# connectors-extension.net
KiCad netlist of a schematic drawn in Altium Designer
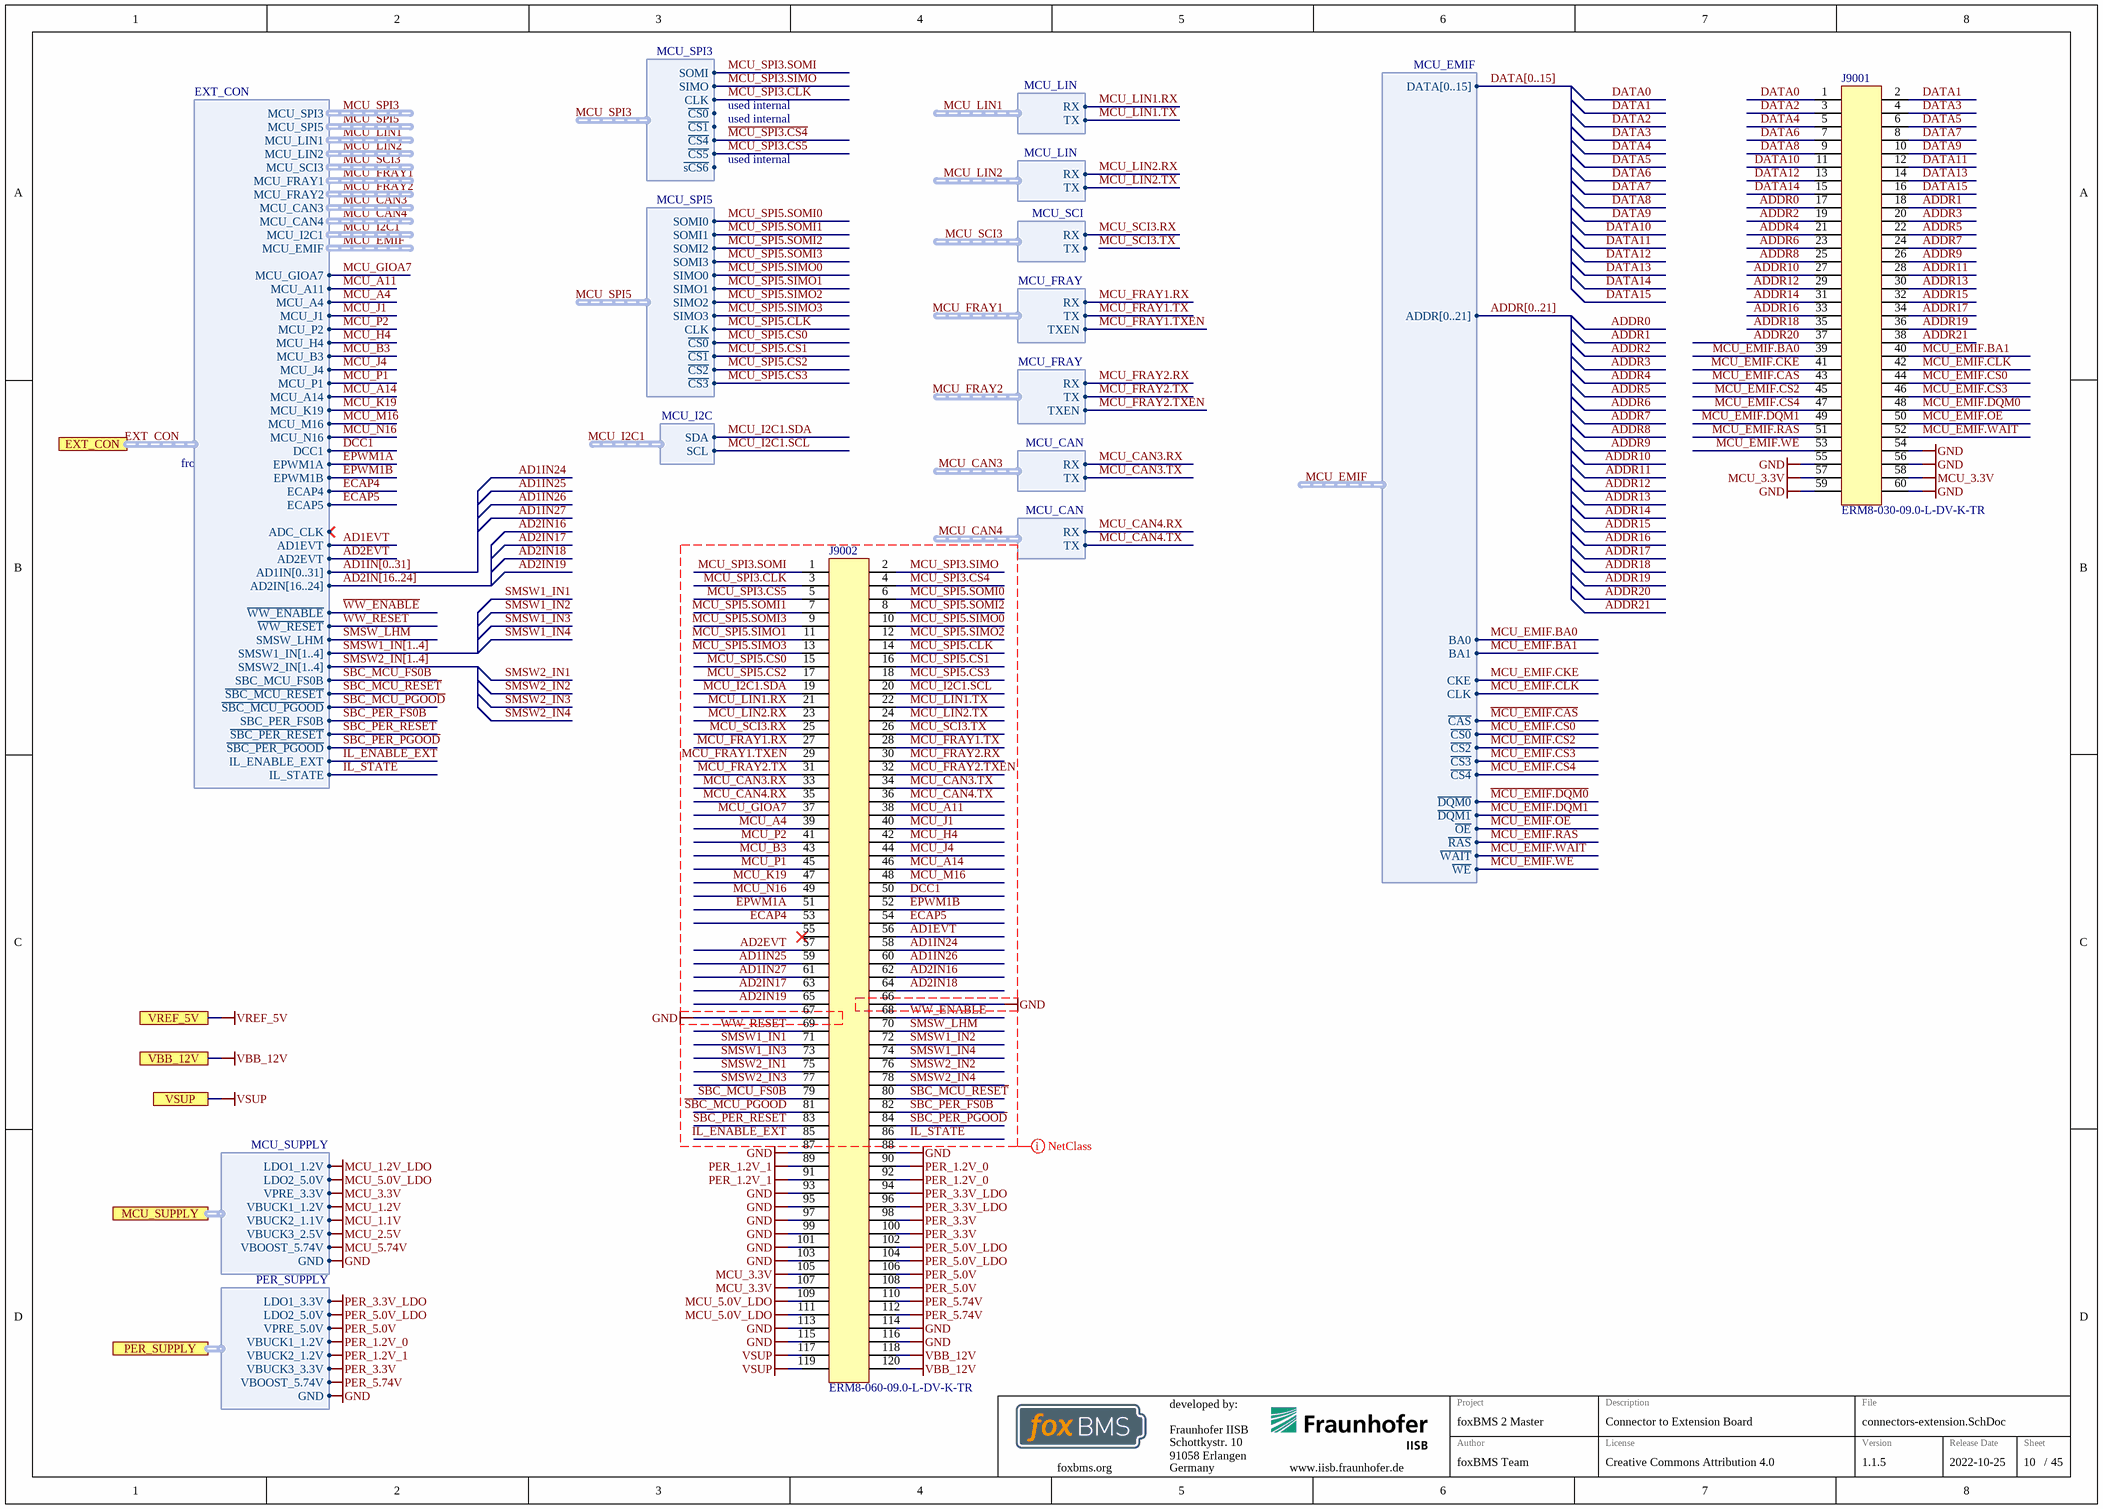
[diagram p0: connectors-extension.SchDoc]

(export (version "E")
  (design (tool "Eeschema 10.0.6"))
  (components
    (comp (ref "J9001")
      (value "ERM8-030-09.0-L-DV-K-TR")
      (footprint "SAMTEC_ERM8-030-09.0-L-DV-K")
      (description "Edge Rate rugged high-speed connector strips")
      (fields
        (field (name "PART NUMBER") "SAMTEC_ERM8-030-09.0-L-DV-K-TR")
        (field (name "MANUFACTURER") "Samtec")
      )
      (libsource (lib "OE750") (part "SAMTEC_ERM8-030-09.0-L-DV-K"))
    )
    (comp (ref "J9002")
      (value "ERM8-060-09.0-L-DV-K-TR")
      (footprint "SAMTEC_ERM8-060-09.0-L-DV-K")
      (description "Edge Rate rugged high-speed connector strips")
      (fields
        (field (name "PART NUMBER") "SAMTEC_ERM8-060-09.0-L-DV-K-TR")
        (field (name "MANUFACTURER") "Samtec")
      )
      (libsource (lib "OE750") (part "SAMTEC_ERM8-060-09.0-L-DV-K"))
    )
  )
  (nets
    (net (code "58") (name "/AD1EVT") (class "Default") (node (ref "J9002") (pin "56") (pintype "passive")))
    (net (code "59") (name "/AD1IN24") (class "Default") (node (ref "J9002") (pin "58") (pintype "passive")))
    (net (code "60") (name "/AD1IN25") (class "Default") (node (ref "J9002") (pin "59") (pintype "passive")))
    (net (code "61") (name "/AD1IN26") (class "Default") (node (ref "J9002") (pin "60") (pintype "passive")))
    (net (code "62") (name "/AD1IN27") (class "Default") (node (ref "J9002") (pin "61") (pintype "passive")))
    (net (code "64") (name "/AD2EVT") (class "Default") (node (ref "J9002") (pin "57") (pintype "passive")))
    (net (code "65") (name "/AD2IN16") (class "Default") (node (ref "J9002") (pin "62") (pintype "passive")))
    (net (code "66") (name "/AD2IN17") (class "Default") (node (ref "J9002") (pin "63") (pintype "passive")))
    (net (code "67") (name "/AD2IN18") (class "Default") (node (ref "J9002") (pin "64") (pintype "passive")))
    (net (code "68") (name "/AD2IN19") (class "Default") (node (ref "J9002") (pin "65") (pintype "passive")))
    (net (code "70") (name "/ADDR0") (class "Default") (node (ref "J9001") (pin "17") (pintype "passive")))
    (net (code "71") (name "/ADDR1") (class "Default") (node (ref "J9001") (pin "18") (pintype "passive")))
    (net (code "72") (name "/ADDR2") (class "Default") (node (ref "J9001") (pin "19") (pintype "passive")))
    (net (code "73") (name "/ADDR3") (class "Default") (node (ref "J9001") (pin "20") (pintype "passive")))
    (net (code "74") (name "/ADDR4") (class "Default") (node (ref "J9001") (pin "21") (pintype "passive")))
    (net (code "75") (name "/ADDR5") (class "Default") (node (ref "J9001") (pin "22") (pintype "passive")))
    (net (code "76") (name "/ADDR6") (class "Default") (node (ref "J9001") (pin "23") (pintype "passive")))
    (net (code "77") (name "/ADDR7") (class "Default") (node (ref "J9001") (pin "24") (pintype "passive")))
    (net (code "78") (name "/ADDR8") (class "Default") (node (ref "J9001") (pin "25") (pintype "passive")))
    (net (code "79") (name "/ADDR9") (class "Default") (node (ref "J9001") (pin "26") (pintype "passive")))
    (net (code "80") (name "/ADDR10") (class "Default") (node (ref "J9001") (pin "27") (pintype "passive")))
    (net (code "81") (name "/ADDR11") (class "Default") (node (ref "J9001") (pin "28") (pintype "passive")))
    (net (code "82") (name "/ADDR12") (class "Default") (node (ref "J9001") (pin "29") (pintype "passive")))
    (net (code "83") (name "/ADDR13") (class "Default") (node (ref "J9001") (pin "30") (pintype "passive")))
    (net (code "84") (name "/ADDR14") (class "Default") (node (ref "J9001") (pin "31") (pintype "passive")))
    (net (code "85") (name "/ADDR15") (class "Default") (node (ref "J9001") (pin "32") (pintype "passive")))
    (net (code "86") (name "/ADDR16") (class "Default") (node (ref "J9001") (pin "33") (pintype "passive")))
    (net (code "87") (name "/ADDR17") (class "Default") (node (ref "J9001") (pin "34") (pintype "passive")))
    (net (code "88") (name "/ADDR18") (class "Default") (node (ref "J9001") (pin "35") (pintype "passive")))
    (net (code "89") (name "/ADDR19") (class "Default") (node (ref "J9001") (pin "36") (pintype "passive")))
    (net (code "90") (name "/ADDR20") (class "Default") (node (ref "J9001") (pin "37") (pintype "passive")))
    (net (code "91") (name "/ADDR21") (class "Default") (node (ref "J9001") (pin "38") (pintype "passive")))
    (net (code "93") (name "/DATA0") (class "Default") (node (ref "J9001") (pin "1") (pintype "passive")))
    (net (code "94") (name "/DATA1") (class "Default") (node (ref "J9001") (pin "2") (pintype "passive")))
    (net (code "95") (name "/DATA2") (class "Default") (node (ref "J9001") (pin "3") (pintype "passive")))
    (net (code "96") (name "/DATA3") (class "Default") (node (ref "J9001") (pin "4") (pintype "passive")))
    (net (code "97") (name "/DATA4") (class "Default") (node (ref "J9001") (pin "5") (pintype "passive")))
    (net (code "98") (name "/DATA5") (class "Default") (node (ref "J9001") (pin "6") (pintype "passive")))
    (net (code "99") (name "/DATA6") (class "Default") (node (ref "J9001") (pin "7") (pintype "passive")))
    (net (code "100") (name "/DATA7") (class "Default") (node (ref "J9001") (pin "8") (pintype "passive")))
    (net (code "101") (name "/DATA8") (class "Default") (node (ref "J9001") (pin "9") (pintype "passive")))
    (net (code "102") (name "/DATA9") (class "Default") (node (ref "J9001") (pin "10") (pintype "passive")))
    (net (code "103") (name "/DATA10") (class "Default") (node (ref "J9001") (pin "11") (pintype "passive")))
    (net (code "104") (name "/DATA11") (class "Default") (node (ref "J9001") (pin "12") (pintype "passive")))
    (net (code "105") (name "/DATA12") (class "Default") (node (ref "J9001") (pin "13") (pintype "passive")))
    (net (code "106") (name "/DATA13") (class "Default") (node (ref "J9001") (pin "14") (pintype "passive")))
    (net (code "107") (name "/DATA14") (class "Default") (node (ref "J9001") (pin "15") (pintype "passive")))
    (net (code "108") (name "/DATA15") (class "Default") (node (ref "J9001") (pin "16") (pintype "passive")))
    (net (code "109") (name "/DCC1") (class "Default") (node (ref "J9002") (pin "50") (pintype "passive")))
    (net (code "110") (name "/ECAP4") (class "Default") (node (ref "J9002") (pin "53") (pintype "passive")))
    (net (code "111") (name "/ECAP5") (class "Default") (node (ref "J9002") (pin "54") (pintype "passive")))
    (net (code "112") (name "/EPWM1A") (class "Default") (node (ref "J9002") (pin "51") (pintype "passive")))
    (net (code "113") (name "/EPWM1B") (class "Default") (node (ref "J9002") (pin "52") (pintype "passive")))
    (net (code "114") (name "/IL_ENABLE_EXT") (class "Default")
      (node (ref "J9002") (pin "85") (pintype "passive"))
    )
    (net (code "115") (name "/IL_STATE") (class "Default")
      (node (ref "J9002") (pin "86") (pintype "passive"))
    )
    (net (code "116") (name "/MCU_A4") (class "Default") (node (ref "J9002") (pin "39") (pintype "passive")))
    (net (code "117") (name "/MCU_A11") (class "Default") (node (ref "J9002") (pin "38") (pintype "passive")))
    (net (code "118") (name "/MCU_A14") (class "Default") (node (ref "J9002") (pin "46") (pintype "passive")))
    (net (code "119") (name "/MCU_B3") (class "Default") (node (ref "J9002") (pin "43") (pintype "passive")))
    (net (code "120") (name "/MCU_CAN3.RX") (class "Default")
      (node (ref "J9002") (pin "33") (pintype "passive"))
    )
    (net (code "121") (name "/MCU_CAN3.TX") (class "Default")
      (node (ref "J9002") (pin "34") (pintype "passive"))
    )
    (net (code "123") (name "/MCU_CAN4.RX") (class "Default")
      (node (ref "J9002") (pin "35") (pintype "passive"))
    )
    (net (code "124") (name "/MCU_CAN4.TX") (class "Default")
      (node (ref "J9002") (pin "36") (pintype "passive"))
    )
    (net (code "126") (name "/MCU_EMIF.BA0") (class "Default")
      (node (ref "J9001") (pin "39") (pintype "passive"))
    )
    (net (code "127") (name "/MCU_EMIF.BA1") (class "Default")
      (node (ref "J9001") (pin "40") (pintype "passive"))
    )
    (net (code "128") (name "/MCU_EMIF.CAS") (class "Default")
      (node (ref "J9001") (pin "43") (pintype "passive"))
    )
    (net (code "129") (name "/MCU_EMIF.CKE") (class "Default")
      (node (ref "J9001") (pin "41") (pintype "passive"))
    )
    (net (code "130") (name "/MCU_EMIF.CLK") (class "Default")
      (node (ref "J9001") (pin "42") (pintype "passive"))
    )
    (net (code "131") (name "/MCU_EMIF.CS0") (class "Default")
      (node (ref "J9001") (pin "44") (pintype "passive"))
    )
    (net (code "132") (name "/MCU_EMIF.CS2") (class "Default")
      (node (ref "J9001") (pin "45") (pintype "passive"))
    )
    (net (code "133") (name "/MCU_EMIF.CS3") (class "Default")
      (node (ref "J9001") (pin "46") (pintype "passive"))
    )
    (net (code "134") (name "/MCU_EMIF.CS4") (class "Default")
      (node (ref "J9001") (pin "47") (pintype "passive"))
    )
    (net (code "135") (name "/MCU_EMIF.DQM0") (class "Default")
      (node (ref "J9001") (pin "48") (pintype "passive"))
    )
    (net (code "136") (name "/MCU_EMIF.DQM1") (class "Default")
      (node (ref "J9001") (pin "49") (pintype "passive"))
    )
    (net (code "137") (name "/MCU_EMIF.OE") (class "Default")
      (node (ref "J9001") (pin "50") (pintype "passive"))
    )
    (net (code "138") (name "/MCU_EMIF.RAS") (class "Default")
      (node (ref "J9001") (pin "51") (pintype "passive"))
    )
    (net (code "139") (name "/MCU_EMIF.WAIT") (class "Default")
      (node (ref "J9001") (pin "52") (pintype "passive"))
    )
    (net (code "140") (name "/MCU_EMIF.WE") (class "Default")
      (node (ref "J9001") (pin "53") (pintype "passive"))
    )
    (net (code "141") (name "/MCU_FRAY1.RX") (class "Default")
      (node (ref "J9002") (pin "27") (pintype "passive"))
    )
    (net (code "142") (name "/MCU_FRAY1.TX") (class "Default")
      (node (ref "J9002") (pin "28") (pintype "passive"))
    )
    (net (code "143") (name "/MCU_FRAY1.TXEN") (class "Default")
      (node (ref "J9002") (pin "29") (pintype "passive"))
    )
    (net (code "145") (name "/MCU_FRAY2.RX") (class "Default")
      (node (ref "J9002") (pin "30") (pintype "passive"))
    )
    (net (code "146") (name "/MCU_FRAY2.TX") (class "Default")
      (node (ref "J9002") (pin "31") (pintype "passive"))
    )
    (net (code "147") (name "/MCU_FRAY2.TXEN") (class "Default")
      (node (ref "J9002") (pin "32") (pintype "passive"))
    )
    (net (code "149") (name "/MCU_GIOA7") (class "Default")
      (node (ref "J9002") (pin "37") (pintype "passive"))
    )
    (net (code "150") (name "/MCU_H4") (class "Default") (node (ref "J9002") (pin "42") (pintype "passive")))
    (net (code "151") (name "/MCU_I2C1.SCL") (class "Default")
      (node (ref "J9002") (pin "20") (pintype "passive"))
    )
    (net (code "152") (name "/MCU_I2C1.SDA") (class "Default")
      (node (ref "J9002") (pin "19") (pintype "passive"))
    )
    (net (code "154") (name "/MCU_J1") (class "Default") (node (ref "J9002") (pin "40") (pintype "passive")))
    (net (code "155") (name "/MCU_J4") (class "Default") (node (ref "J9002") (pin "44") (pintype "passive")))
    (net (code "156") (name "/MCU_K19") (class "Default") (node (ref "J9002") (pin "47") (pintype "passive")))
    (net (code "157") (name "/MCU_LIN1.RX") (class "Default")
      (node (ref "J9002") (pin "21") (pintype "passive"))
    )
    (net (code "158") (name "/MCU_LIN1.TX") (class "Default")
      (node (ref "J9002") (pin "22") (pintype "passive"))
    )
    (net (code "160") (name "/MCU_LIN2.RX") (class "Default")
      (node (ref "J9002") (pin "23") (pintype "passive"))
    )
    (net (code "161") (name "/MCU_LIN2.TX") (class "Default")
      (node (ref "J9002") (pin "24") (pintype "passive"))
    )
    (net (code "163") (name "/MCU_M16") (class "Default") (node (ref "J9002") (pin "48") (pintype "passive")))
    (net (code "164") (name "/MCU_N16") (class "Default") (node (ref "J9002") (pin "49") (pintype "passive")))
    (net (code "165") (name "/MCU_P1") (class "Default") (node (ref "J9002") (pin "45") (pintype "passive")))
    (net (code "166") (name "/MCU_P2") (class "Default") (node (ref "J9002") (pin "41") (pintype "passive")))
    (net (code "167") (name "/MCU_SCI3.RX") (class "Default")
      (node (ref "J9002") (pin "25") (pintype "passive"))
    )
    (net (code "168") (name "/MCU_SCI3.TX") (class "Default")
      (node (ref "J9002") (pin "26") (pintype "passive"))
    )
    (net (code "170") (name "/MCU_SPI3.CLK") (class "Default")
      (node (ref "J9002") (pin "3") (pintype "passive"))
    )
    (net (code "171") (name "/MCU_SPI3.CS4") (class "Default")
      (node (ref "J9002") (pin "4") (pintype "passive"))
    )
    (net (code "172") (name "/MCU_SPI3.CS5") (class "Default")
      (node (ref "J9002") (pin "5") (pintype "passive"))
    )
    (net (code "173") (name "/MCU_SPI3.SIMO") (class "Default")
      (node (ref "J9002") (pin "2") (pintype "passive"))
    )
    (net (code "174") (name "/MCU_SPI3.SOMI") (class "Default")
      (node (ref "J9002") (pin "1") (pintype "passive"))
    )
    (net (code "176") (name "/MCU_SPI5.CLK") (class "Default")
      (node (ref "J9002") (pin "14") (pintype "passive"))
    )
    (net (code "177") (name "/MCU_SPI5.CS0") (class "Default")
      (node (ref "J9002") (pin "15") (pintype "passive"))
    )
    (net (code "178") (name "/MCU_SPI5.CS1") (class "Default")
      (node (ref "J9002") (pin "16") (pintype "passive"))
    )
    (net (code "179") (name "/MCU_SPI5.CS2") (class "Default")
      (node (ref "J9002") (pin "17") (pintype "passive"))
    )
    (net (code "180") (name "/MCU_SPI5.CS3") (class "Default")
      (node (ref "J9002") (pin "18") (pintype "passive"))
    )
    (net (code "181") (name "/MCU_SPI5.SIMO0") (class "Default")
      (node (ref "J9002") (pin "10") (pintype "passive"))
    )
    (net (code "182") (name "/MCU_SPI5.SIMO1") (class "Default")
      (node (ref "J9002") (pin "11") (pintype "passive"))
    )
    (net (code "183") (name "/MCU_SPI5.SIMO2") (class "Default")
      (node (ref "J9002") (pin "12") (pintype "passive"))
    )
    (net (code "184") (name "/MCU_SPI5.SIMO3") (class "Default")
      (node (ref "J9002") (pin "13") (pintype "passive"))
    )
    (net (code "185") (name "/MCU_SPI5.SOMI0") (class "Default")
      (node (ref "J9002") (pin "6") (pintype "passive"))
    )
    (net (code "186") (name "/MCU_SPI5.SOMI1") (class "Default")
      (node (ref "J9002") (pin "7") (pintype "passive"))
    )
    (net (code "187") (name "/MCU_SPI5.SOMI2") (class "Default")
      (node (ref "J9002") (pin "8") (pintype "passive"))
    )
    (net (code "188") (name "/MCU_SPI5.SOMI3") (class "Default")
      (node (ref "J9002") (pin "9") (pintype "passive"))
    )
    (net (code "190") (name "/SBC_MCU_FS0B") (class "Default")
      (node (ref "J9002") (pin "79") (pintype "passive"))
    )
    (net (code "191") (name "/SBC_MCU_PGOOD") (class "Default")
      (node (ref "J9002") (pin "81") (pintype "passive"))
    )
    (net (code "192") (name "/SBC_MCU_RESET") (class "Default")
      (node (ref "J9002") (pin "80") (pintype "passive"))
    )
    (net (code "193") (name "/SBC_PER_FS0B") (class "Default")
      (node (ref "J9002") (pin "82") (pintype "passive"))
    )
    (net (code "194") (name "/SBC_PER_PGOOD") (class "Default")
      (node (ref "J9002") (pin "84") (pintype "passive"))
    )
    (net (code "195") (name "/SBC_PER_RESET") (class "Default")
      (node (ref "J9002") (pin "83") (pintype "passive"))
    )
    (net (code "196") (name "/SMSW1_IN1") (class "Default")
      (node (ref "J9002") (pin "71") (pintype "passive"))
    )
    (net (code "197") (name "/SMSW1_IN2") (class "Default")
      (node (ref "J9002") (pin "72") (pintype "passive"))
    )
    (net (code "198") (name "/SMSW1_IN3") (class "Default")
      (node (ref "J9002") (pin "73") (pintype "passive"))
    )
    (net (code "199") (name "/SMSW1_IN4") (class "Default")
      (node (ref "J9002") (pin "74") (pintype "passive"))
    )
    (net (code "201") (name "/SMSW2_IN1") (class "Default")
      (node (ref "J9002") (pin "75") (pintype "passive"))
    )
    (net (code "202") (name "/SMSW2_IN2") (class "Default")
      (node (ref "J9002") (pin "76") (pintype "passive"))
    )
    (net (code "203") (name "/SMSW2_IN3") (class "Default")
      (node (ref "J9002") (pin "77") (pintype "passive"))
    )
    (net (code "204") (name "/SMSW2_IN4") (class "Default")
      (node (ref "J9002") (pin "78") (pintype "passive"))
    )
    (net (code "205") (name "/SMSW_LHM") (class "Default")
      (node (ref "J9002") (pin "70") (pintype "passive"))
    )
    (net (code "206") (name "/WW_ENABLE") (class "Default")
      (node (ref "J9002") (pin "68") (pintype "passive"))
    )
    (net (code "207") (name "/WW_RESET") (class "Default")
      (node (ref "J9002") (pin "69") (pintype "passive"))
    )
    (net (code "224") (name "GND") (class "Default")
      (node (ref "J9001") (pin "54") (pintype "passive"))
      (node (ref "J9001") (pin "55") (pintype "passive"))
      (node (ref "J9001") (pin "56") (pintype "passive"))
      (node (ref "J9001") (pin "59") (pintype "passive"))
      (node (ref "J9001") (pin "60") (pintype "passive"))
      (node (ref "J9002") (pin "101") (pintype "passive"))
      (node (ref "J9002") (pin "103") (pintype "passive"))
      (node (ref "J9002") (pin "113") (pintype "passive"))
      (node (ref "J9002") (pin "114") (pintype "passive"))
      (node (ref "J9002") (pin "115") (pintype "passive"))
      (node (ref "J9002") (pin "116") (pintype "passive"))
      (node (ref "J9002") (pin "66") (pintype "passive"))
      (node (ref "J9002") (pin "67") (pintype "passive"))
      (node (ref "J9002") (pin "87") (pintype "passive"))
      (node (ref "J9002") (pin "88") (pintype "passive"))
      (node (ref "J9002") (pin "93") (pintype "passive"))
      (node (ref "J9002") (pin "95") (pintype "passive"))
      (node (ref "J9002") (pin "97") (pintype "passive"))
      (node (ref "J9002") (pin "99") (pintype "passive"))
    )
    (net (code "229") (name "MCU_3.3V") (class "Default")
      (node (ref "J9001") (pin "57") (pintype "passive"))
      (node (ref "J9001") (pin "58") (pintype "passive"))
      (node (ref "J9002") (pin "105") (pintype "passive"))
      (node (ref "J9002") (pin "107") (pintype "passive"))
    )
    (net (code "230") (name "MCU_5.0V_LDO") (class "Default")
      (node (ref "J9002") (pin "109") (pintype "passive"))
      (node (ref "J9002") (pin "111") (pintype "passive"))
    )
    (net (code "232") (name "PER_1.2V_0") (class "Default")
      (node (ref "J9002") (pin "90") (pintype "passive"))
      (node (ref "J9002") (pin "92") (pintype "passive"))
    )
    (net (code "233") (name "PER_1.2V_1") (class "Default")
      (node (ref "J9002") (pin "89") (pintype "passive"))
      (node (ref "J9002") (pin "91") (pintype "passive"))
    )
    (net (code "234") (name "PER_3.3V") (class "Default")
      (node (ref "J9002") (pin "100") (pintype "passive"))
      (node (ref "J9002") (pin "98") (pintype "passive"))
    )
    (net (code "235") (name "PER_3.3V_LDO") (class "Default")
      (node (ref "J9002") (pin "94") (pintype "passive"))
      (node (ref "J9002") (pin "96") (pintype "passive"))
    )
    (net (code "236") (name "PER_5.0V") (class "Default")
      (node (ref "J9002") (pin "106") (pintype "passive"))
      (node (ref "J9002") (pin "108") (pintype "passive"))
    )
    (net (code "237") (name "PER_5.0V_LDO") (class "Default")
      (node (ref "J9002") (pin "102") (pintype "passive"))
      (node (ref "J9002") (pin "104") (pintype "passive"))
    )
    (net (code "238") (name "PER_5.74V") (class "Default")
      (node (ref "J9002") (pin "110") (pintype "passive"))
      (node (ref "J9002") (pin "112") (pintype "passive"))
    )
    (net (code "239") (name "VBB_12V") (class "Default")
      (node (ref "J9002") (pin "118") (pintype "passive"))
      (node (ref "J9002") (pin "120") (pintype "passive"))
    )
    (net (code "241") (name "VSUP") (class "Default")
      (node (ref "J9002") (pin "117") (pintype "passive"))
      (node (ref "J9002") (pin "119") (pintype "passive"))
    )
    (net (code "242") (name "unconnected-(J9002-Pad55)") (class "Default")
      (node (ref "J9002") (pin "55") (pintype "passive+no_connect"))
    )
  )
)
